# Buttons.net
KiCad netlist of a schematic drawn in Altium Designer
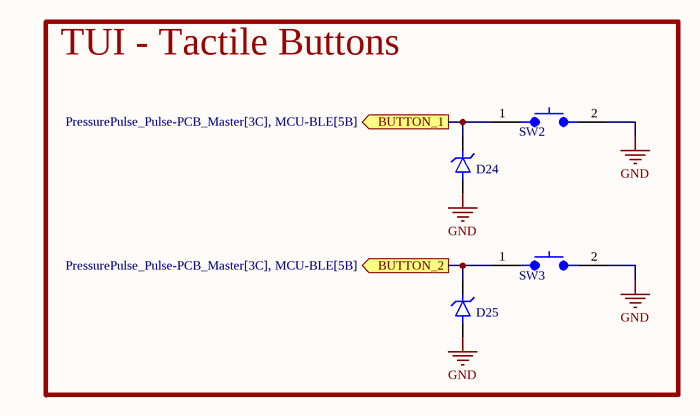
[diagram p0: Buttons.SchDoc]

(export (version "E")
  (design (tool "Eeschema 10.0.6"))
  (components
    (comp (ref "D24")
      (value "BDFN2C051V40")
      (footprint "PressurePulse:BDFN2C051V40")
      (description "25V Clamp 4A (8/20µs) Ipp Tvs Diode Surface Mount SLP1006P2")
      (fields (field (name "MFR") "BORN"))
      (libsource (lib "PressurePulse") (part "TVS DIODE"))
    )
    (comp (ref "D25")
      (value "BDFN2C051V40")
      (footprint "PressurePulse:BDFN2C051V40")
      (description "25V Clamp 4A (8/20µs) Ipp Tvs Diode Surface Mount SLP1006P2")
      (fields (field (name "MFR") "BORN"))
      (libsource (lib "PressurePulse") (part "TVS DIODE"))
    )
    (comp (ref "SW2")
      (value "SPST SMT Tactile Push Button Switch")
      (footprint "PressurePulse:TL3302BF180QJ")
      (fields (field (name "MFR") "E-Switch"))
      (libsource (lib "PressurePulse") (part "SPST SMT Tactile Push Button Switch"))
    )
    (comp (ref "SW3")
      (value "SPST SMT Tactile Push Button Switch")
      (footprint "PressurePulse:TL3302BF180QJ")
      (fields (field (name "MFR") "E-Switch"))
      (libsource (lib "PressurePulse") (part "SPST SMT Tactile Push Button Switch"))
    )
  )
  (nets
    (net (code "1") (name "/BUTTON_1") (class "Default")
      (node (ref "D24") (pin "K") (pinfunction "K_K") (pintype "passive"))
      (node (ref "SW2") (pin "1") (pinfunction "1_1") (pintype "passive"))
    )
    (net (code "2") (name "/BUTTON_2") (class "Default")
      (node (ref "D25") (pin "K") (pinfunction "K_K") (pintype "passive"))
      (node (ref "SW3") (pin "1") (pinfunction "1_1") (pintype "passive"))
    )
    (net (code "3") (name "GND") (class "Default")
      (node (ref "D24") (pin "A") (pinfunction "A_A") (pintype "passive"))
      (node (ref "D25") (pin "A") (pinfunction "A_A") (pintype "passive"))
      (node (ref "SW2") (pin "2") (pinfunction "3_2") (pintype "passive"))
      (node (ref "SW3") (pin "2") (pinfunction "3_2") (pintype "passive"))
    )
  )
)
